# the_vert_annotated.net
KiCad netlist of a schematic drawn in EAGLE
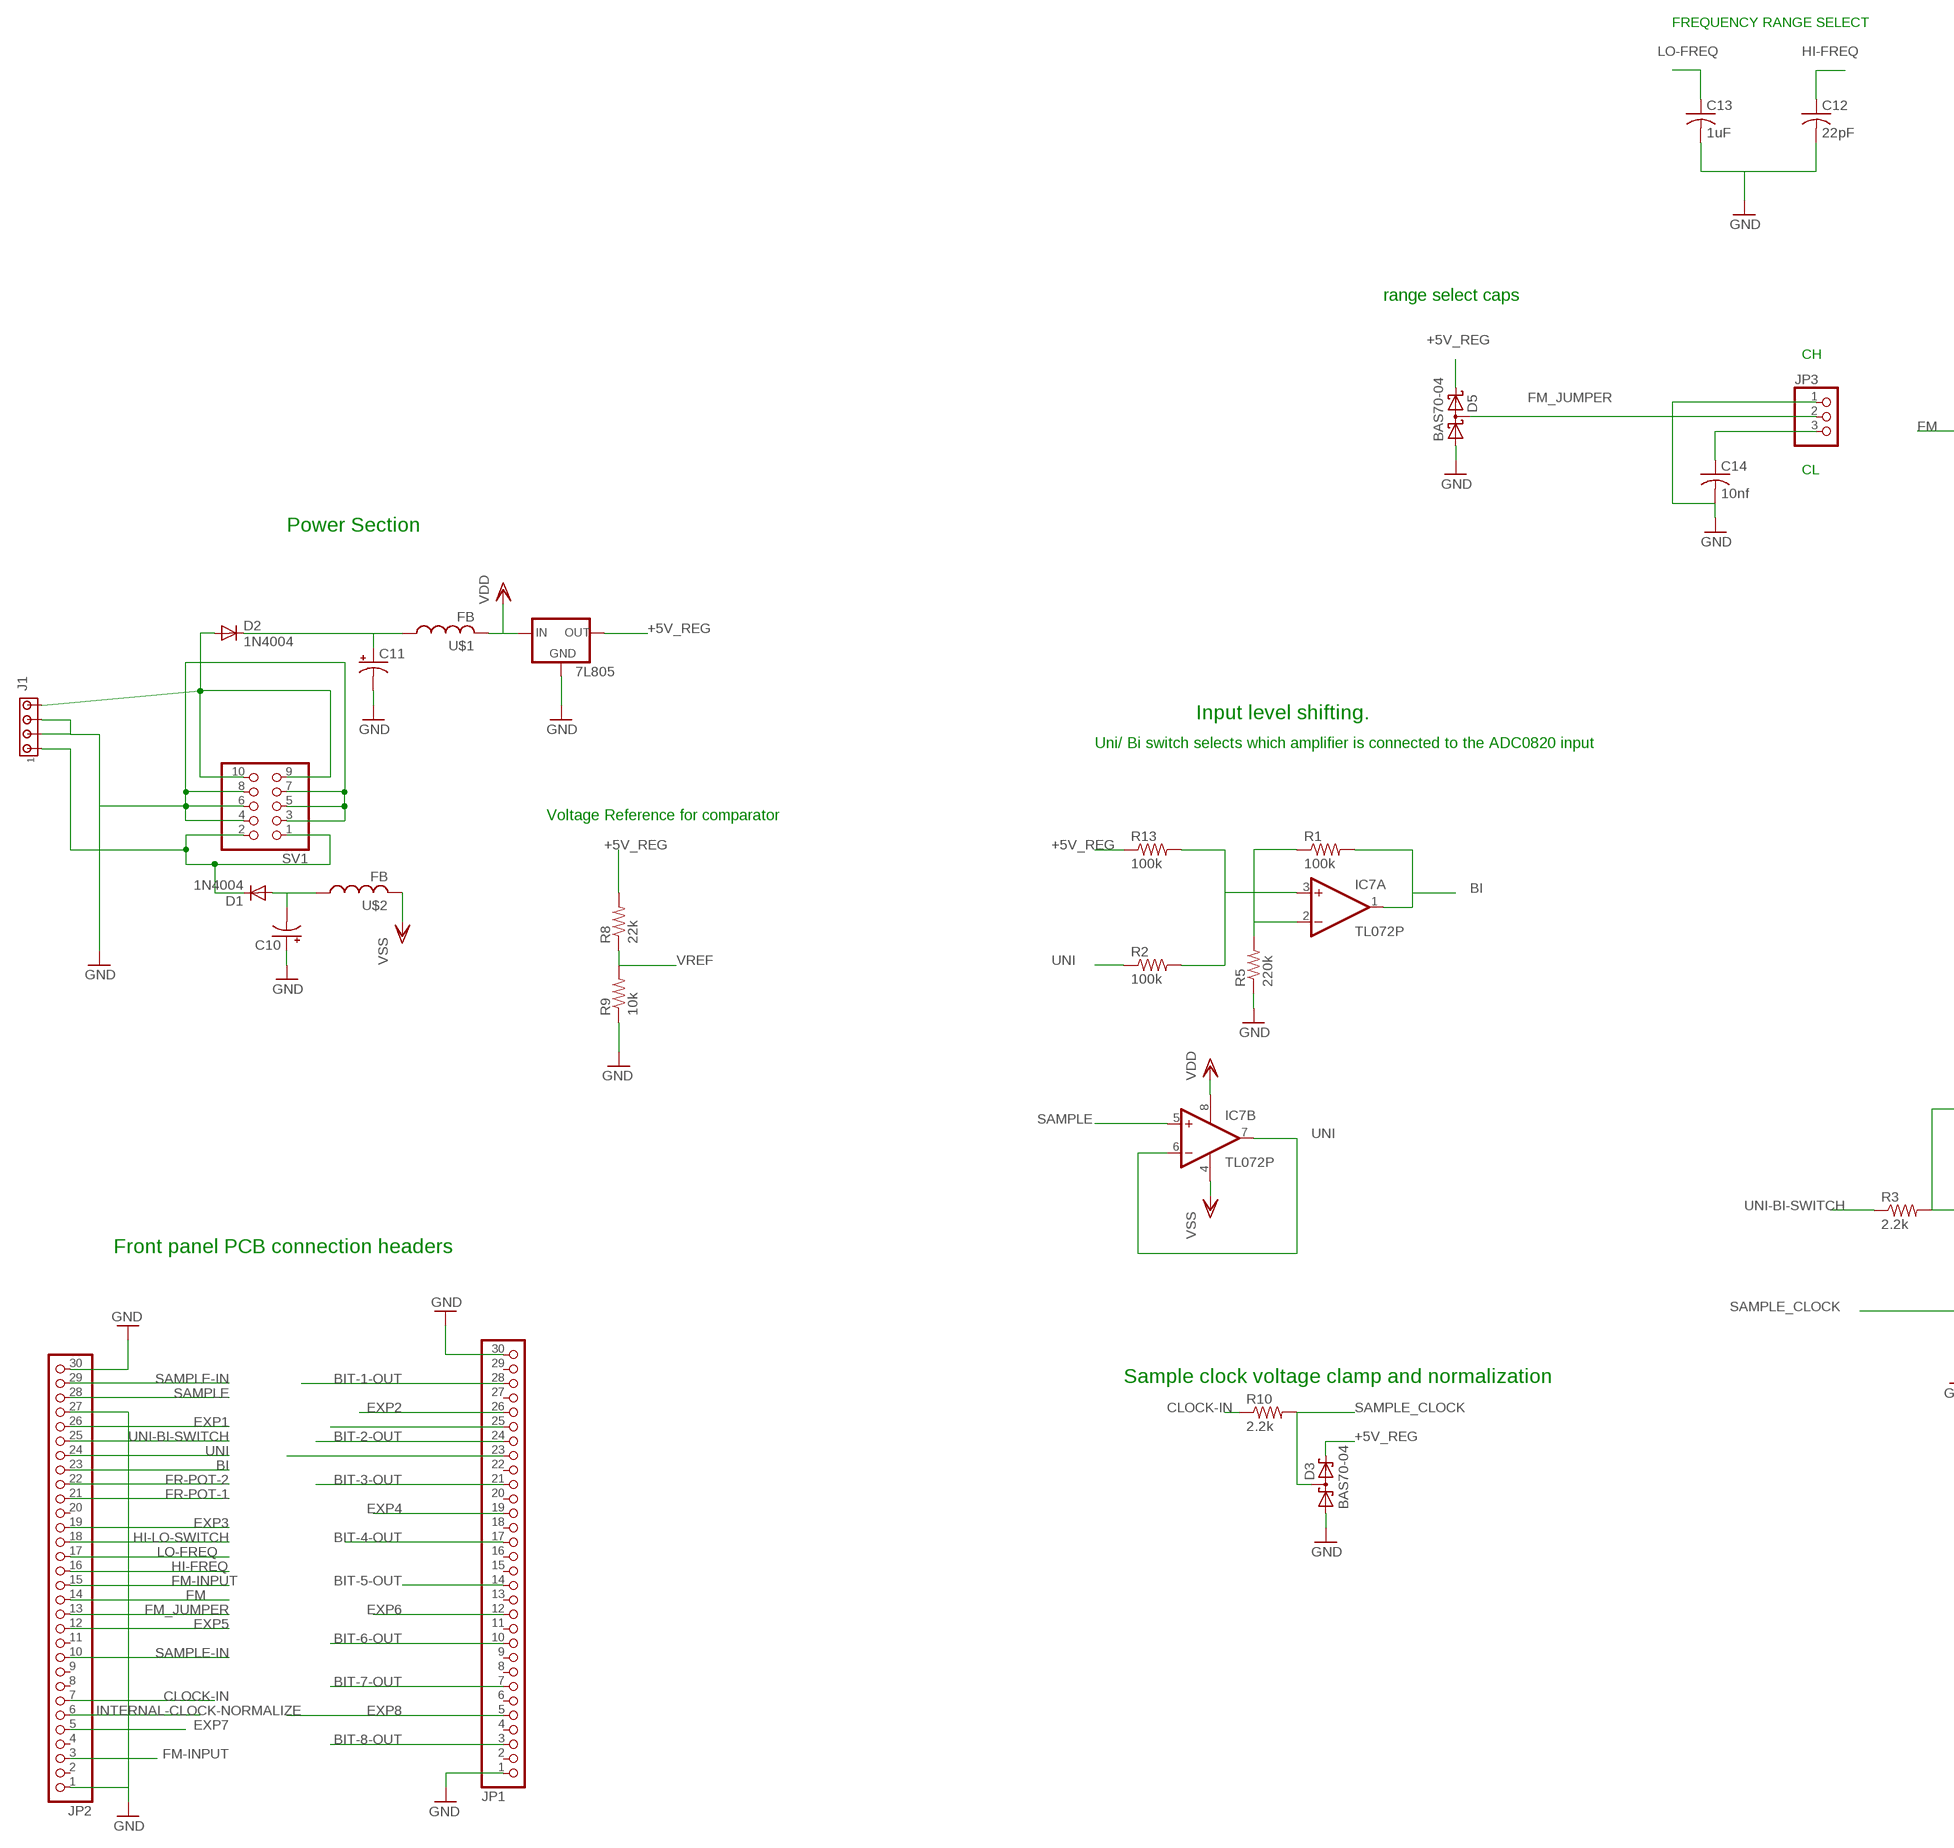
[diagram p0: schematic, sheet 1, part 1 of 2]
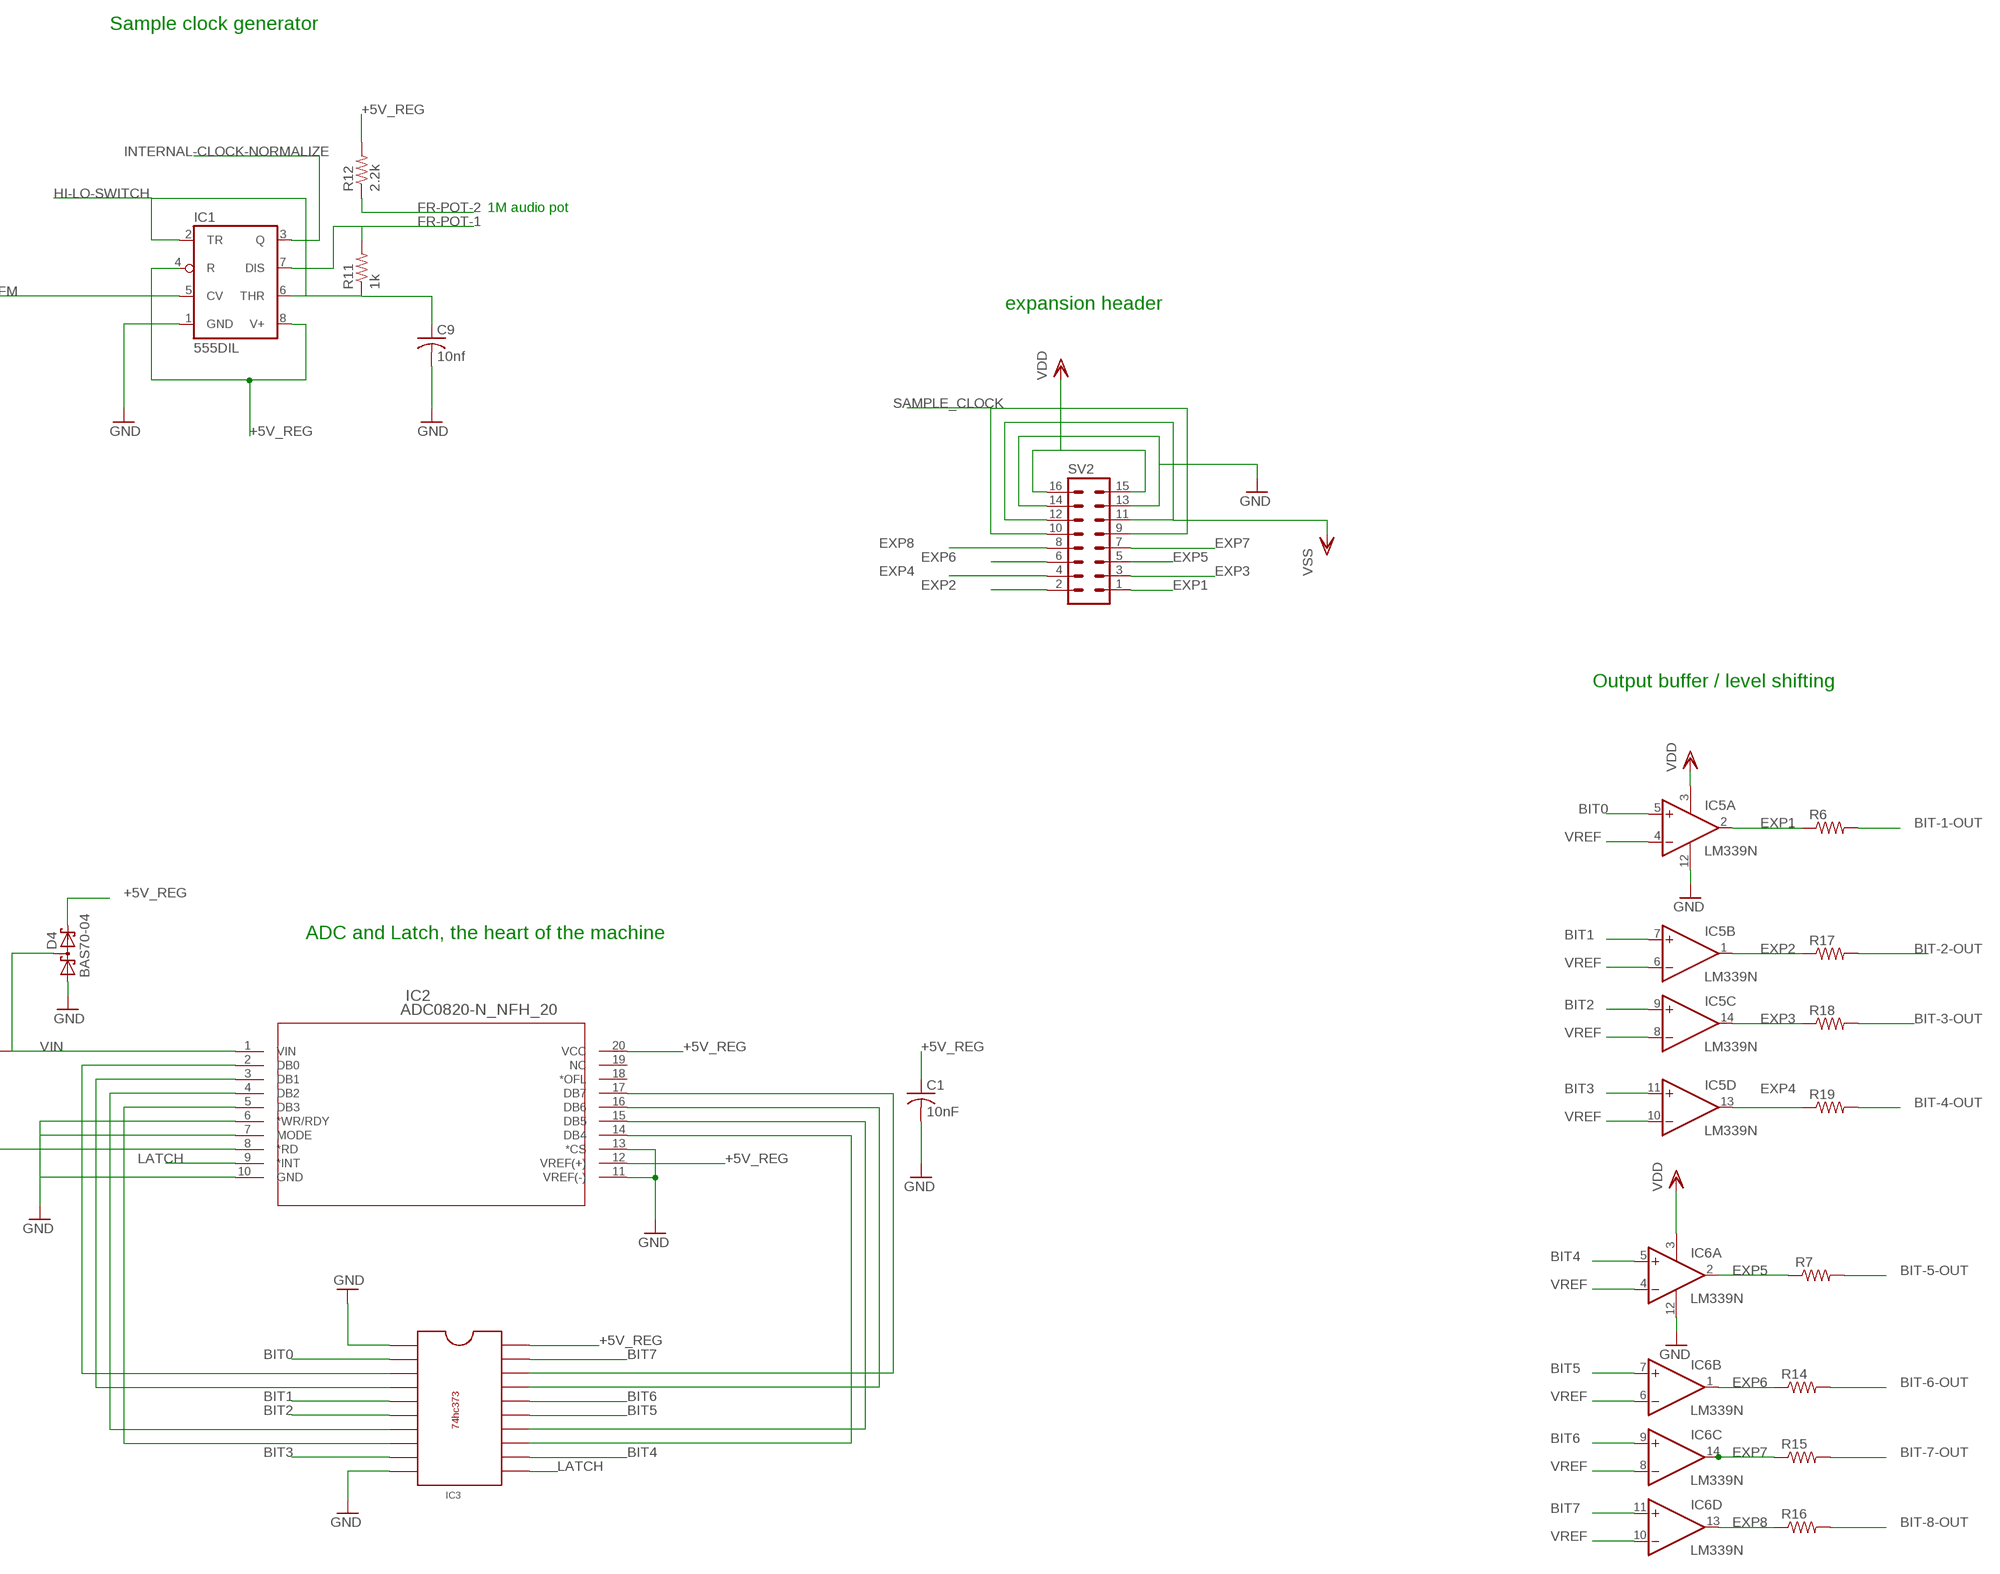
[diagram p1: schematic, sheet 1, part 2 of 2]

(export (version "E")
  (design (tool "Eeschema 10.0.6"))
  (components
    (comp (ref "7L805")
      (value "78LXX")
      (footprint "eagle-import:78LXX")
      (libsource (lib "eagle-import") (part "78LXX"))
    )
    (comp (ref "C1")
      (value "10nF")
      (footprint "eagle-import:C1206")
      (libsource (lib "eagle-import") (part "C-USC1206"))
    )
    (comp (ref "C9")
      (value "10nf")
      (footprint "eagle-import:C1206")
      (libsource (lib "eagle-import") (part "C-USC1206"))
    )
    (comp (ref "C10")
      (value "CPOL-USE5-5")
      (footprint "eagle-import:E5-5")
      (libsource (lib "eagle-import") (part "CPOL-USE5-5"))
    )
    (comp (ref "C11")
      (value "CPOL-USE5-5")
      (footprint "eagle-import:E5-5")
      (libsource (lib "eagle-import") (part "CPOL-USE5-5"))
    )
    (comp (ref "C12")
      (value "22pF")
      (footprint "eagle-import:C1206")
      (libsource (lib "eagle-import") (part "C-USC1206"))
    )
    (comp (ref "C13")
      (value "1uF")
      (footprint "eagle-import:C1206")
      (libsource (lib "eagle-import") (part "C-USC1206"))
    )
    (comp (ref "C14")
      (value "10nf")
      (footprint "eagle-import:C1206")
      (libsource (lib "eagle-import") (part "C-USC1206"))
    )
    (comp (ref "D1")
      (value "1N4004")
      (footprint "eagle-import:DO41-10")
      (libsource (lib "eagle-import") (part "1N4004"))
    )
    (comp (ref "D2")
      (value "1N4004")
      (footprint "eagle-import:DO41-10")
      (libsource (lib "eagle-import") (part "1N4004"))
    )
    (comp (ref "D3")
      (value "BAS70-04")
      (footprint "eagle-import:SOT23")
      (libsource (lib "eagle-import") (part "BAS70-04"))
    )
    (comp (ref "D4")
      (value "BAS70-04")
      (footprint "eagle-import:SOT23")
      (libsource (lib "eagle-import") (part "BAS70-04"))
    )
    (comp (ref "D5")
      (value "BAS70-04")
      (footprint "eagle-import:SOT23")
      (libsource (lib "eagle-import") (part "BAS70-04"))
    )
    (comp (ref "IC1")
      (value "555DIL")
      (footprint "eagle-import:DIL08")
      (libsource (lib "eagle-import") (part "555DIL"))
    )
    (comp (ref "IC2")
      (value "ADC0820-N_NFH_20")
      (footprint "eagle-import:NFH20")
      (fields (field (name "MANUFACTURER_PART_NUMBER") "adc0820_dw_20"))
      (libsource (lib "eagle-import") (part "ADC0820-N_NFH_20"))
    )
    (comp (ref "IC3")
      (value "74HC373")
      (footprint "eagle-import:DIL20")
      (libsource (lib "eagle-import") (part "74HC373"))
    )
    (comp (ref "IC5")
      (value "LM339N")
      (footprint "eagle-import:DIL14")
      (libsource (lib "eagle-import") (part "LM339N"))
    )
    (comp (ref "IC6")
      (value "LM339N")
      (footprint "eagle-import:DIL14")
      (libsource (lib "eagle-import") (part "LM339N"))
    )
    (comp (ref "IC7")
      (value "TL072P")
      (footprint "eagle-import:DIL08")
      (libsource (lib "eagle-import") (part "TL072P"))
    )
    (comp (ref "J1")
      (value "MTA04-156")
      (footprint "eagle-import:1X4MTA")
      (libsource (lib "eagle-import") (part "MTA04-156"))
    )
    (comp (ref "JP1")
      (value "PINHD-1X30")
      (footprint "eagle-import:1X30")
      (libsource (lib "eagle-import") (part "PINHD-1X30"))
    )
    (comp (ref "JP2")
      (value "PINHD-1X30")
      (footprint "eagle-import:1X30")
      (libsource (lib "eagle-import") (part "PINHD-1X30"))
    )
    (comp (ref "JP3")
      (value "PINHD-1X3")
      (footprint "eagle-import:1X03")
      (libsource (lib "eagle-import") (part "PINHD-1X3"))
    )
    (comp (ref "R1")
      (value "100k")
      (footprint "eagle-import:R1206")
      (libsource (lib "eagle-import") (part "R-US_R1206"))
    )
    (comp (ref "R2")
      (value "100k")
      (footprint "eagle-import:R1206")
      (libsource (lib "eagle-import") (part "R-US_R1206"))
    )
    (comp (ref "R3")
      (value "2.2k")
      (footprint "eagle-import:R1206")
      (libsource (lib "eagle-import") (part "R-US_R1206"))
    )
    (comp (ref "R5")
      (value "220k")
      (footprint "eagle-import:R1206")
      (libsource (lib "eagle-import") (part "R-US_R1206"))
    )
    (comp (ref "R6")
      (value "R-US_R1206")
      (footprint "eagle-import:R1206")
      (libsource (lib "eagle-import") (part "R-US_R1206"))
    )
    (comp (ref "R7")
      (value "R-US_R1206")
      (footprint "eagle-import:R1206")
      (libsource (lib "eagle-import") (part "R-US_R1206"))
    )
    (comp (ref "R8")
      (value "22k")
      (footprint "eagle-import:R1206")
      (libsource (lib "eagle-import") (part "R-US_R1206"))
    )
    (comp (ref "R9")
      (value "10k")
      (footprint "eagle-import:R1206")
      (libsource (lib "eagle-import") (part "R-US_R1206"))
    )
    (comp (ref "R10")
      (value "2.2k")
      (footprint "eagle-import:R1206")
      (libsource (lib "eagle-import") (part "R-US_R1206"))
    )
    (comp (ref "R11")
      (value "1k")
      (footprint "eagle-import:R1206")
      (libsource (lib "eagle-import") (part "R-US_R1206"))
    )
    (comp (ref "R12")
      (value "2.2k")
      (footprint "eagle-import:R1206")
      (libsource (lib "eagle-import") (part "R-US_R1206"))
    )
    (comp (ref "R13")
      (value "100k")
      (footprint "eagle-import:R1206")
      (libsource (lib "eagle-import") (part "R-US_R1206"))
    )
    (comp (ref "R14")
      (value "R-US_R1206")
      (footprint "eagle-import:R1206")
      (libsource (lib "eagle-import") (part "R-US_R1206"))
    )
    (comp (ref "R15")
      (value "R-US_R1206")
      (footprint "eagle-import:R1206")
      (libsource (lib "eagle-import") (part "R-US_R1206"))
    )
    (comp (ref "R16")
      (value "R-US_R1206")
      (footprint "eagle-import:R1206")
      (libsource (lib "eagle-import") (part "R-US_R1206"))
    )
    (comp (ref "R17")
      (value "R-US_R1206")
      (footprint "eagle-import:R1206")
      (libsource (lib "eagle-import") (part "R-US_R1206"))
    )
    (comp (ref "R18")
      (value "R-US_R1206")
      (footprint "eagle-import:R1206")
      (libsource (lib "eagle-import") (part "R-US_R1206"))
    )
    (comp (ref "R19")
      (value "R-US_R1206")
      (footprint "eagle-import:R1206")
      (libsource (lib "eagle-import") (part "R-US_R1206"))
    )
    (comp (ref "SV1")
      (value "PINHD-2X5")
      (footprint "eagle-import:2X05")
      (libsource (lib "eagle-import") (part "PINHD-2X5"))
    )
    (comp (ref "SV2")
      (value "MA08-2")
      (footprint "eagle-import:MA08-2")
      (libsource (lib "eagle-import") (part "MA08-2"))
    )
    (comp (ref "U$1") (value "FB") (footprint "eagle-import:FB") (libsource (lib "eagle-import") (part "FB")))
    (comp (ref "U$2") (value "FB") (footprint "eagle-import:FB") (libsource (lib "eagle-import") (part "FB")))
  )
  (nets
    (net (code "1") (name "/+5V_REG") (class "Default")
      (node (ref "7L805") (pin "OUT") (pinfunction "OUT_OUT") (pintype "passive"))
      (node (ref "C1") (pin "1") (pinfunction "1_1") (pintype "passive"))
      (node (ref "D3") (pin "2") (pinfunction "C2_2") (pintype "passive"))
      (node (ref "D4") (pin "2") (pinfunction "C2_2") (pintype "passive"))
      (node (ref "D5") (pin "2") (pinfunction "C2_2") (pintype "passive"))
      (node (ref "IC1") (pin "4") (pinfunction "R_4") (pintype "input"))
      (node (ref "IC1") (pin "8") (pinfunction "V+_8") (pintype "power_in"))
      (node (ref "IC2") (pin "12") (pinfunction "VREF(+)_12") (pintype "power_in"))
      (node (ref "IC2") (pin "20") (pinfunction "VCC_20") (pintype "power_in"))
      (node (ref "IC3") (pin "20") (pinfunction "20_20") (pintype "bidirectional"))
      (node (ref "R12") (pin "2") (pinfunction "2_2") (pintype "passive"))
      (node (ref "R13") (pin "1") (pinfunction "1_1") (pintype "passive"))
      (node (ref "R8") (pin "2") (pinfunction "2_2") (pintype "passive"))
    )
    (net (code "2") (name "/BI") (class "Default")
      (node (ref "IC7") (pin "1") (pinfunction "OUT_1") (pintype "output"))
      (node (ref "JP2") (pin "23") (pinfunction "23_23") (pintype "passive"))
      (node (ref "R1") (pin "2") (pinfunction "2_2") (pintype "passive"))
    )
    (net (code "3") (name "/BIT-1-OUT") (class "Default")
      (node (ref "JP1") (pin "28") (pinfunction "28_28") (pintype "passive"))
      (node (ref "R6") (pin "2") (pinfunction "2_2") (pintype "passive"))
    )
    (net (code "4") (name "/BIT-2-OUT") (class "Default")
      (node (ref "JP1") (pin "24") (pinfunction "24_24") (pintype "passive"))
      (node (ref "R17") (pin "2") (pinfunction "2_2") (pintype "passive"))
    )
    (net (code "5") (name "/BIT-3-OUT") (class "Default")
      (node (ref "JP1") (pin "21") (pinfunction "21_21") (pintype "passive"))
      (node (ref "R18") (pin "2") (pinfunction "2_2") (pintype "passive"))
    )
    (net (code "6") (name "/BIT-4-OUT") (class "Default")
      (node (ref "JP1") (pin "17") (pinfunction "17_17") (pintype "passive"))
      (node (ref "R19") (pin "2") (pinfunction "2_2") (pintype "passive"))
    )
    (net (code "7") (name "/BIT-5-OUT") (class "Default")
      (node (ref "JP1") (pin "14") (pinfunction "14_14") (pintype "passive"))
      (node (ref "R7") (pin "2") (pinfunction "2_2") (pintype "passive"))
    )
    (net (code "8") (name "/BIT-6-OUT") (class "Default")
      (node (ref "JP1") (pin "10") (pinfunction "10_10") (pintype "passive"))
      (node (ref "R14") (pin "2") (pinfunction "2_2") (pintype "passive"))
    )
    (net (code "9") (name "/BIT-7-OUT") (class "Default")
      (node (ref "JP1") (pin "7") (pinfunction "7_7") (pintype "passive"))
      (node (ref "R15") (pin "2") (pinfunction "2_2") (pintype "passive"))
    )
    (net (code "10") (name "/BIT-8-OUT") (class "Default")
      (node (ref "JP1") (pin "3") (pinfunction "3_3") (pintype "passive"))
      (node (ref "R16") (pin "2") (pinfunction "2_2") (pintype "passive"))
    )
    (net (code "11") (name "/BIT0") (class "Default")
      (node (ref "IC3") (pin "2") (pinfunction "2_2") (pintype "bidirectional"))
      (node (ref "IC5") (pin "5") (pinfunction "+IN_5") (pintype "input"))
    )
    (net (code "12") (name "/BIT1") (class "Default")
      (node (ref "IC3") (pin "5") (pinfunction "5_5") (pintype "bidirectional"))
      (node (ref "IC5") (pin "7") (pinfunction "+IN_7") (pintype "input"))
    )
    (net (code "13") (name "/BIT2") (class "Default")
      (node (ref "IC3") (pin "6") (pinfunction "6_6") (pintype "bidirectional"))
      (node (ref "IC5") (pin "9") (pinfunction "+IN_9") (pintype "input"))
    )
    (net (code "14") (name "/BIT3") (class "Default")
      (node (ref "IC3") (pin "9") (pinfunction "9_9") (pintype "bidirectional"))
      (node (ref "IC5") (pin "11") (pinfunction "+IN_11") (pintype "input"))
    )
    (net (code "15") (name "/BIT4") (class "Default")
      (node (ref "IC3") (pin "12") (pinfunction "12_12") (pintype "bidirectional"))
      (node (ref "IC6") (pin "5") (pinfunction "+IN_5") (pintype "input"))
    )
    (net (code "16") (name "/BIT5") (class "Default")
      (node (ref "IC3") (pin "15") (pinfunction "15_15") (pintype "bidirectional"))
      (node (ref "IC6") (pin "7") (pinfunction "+IN_7") (pintype "input"))
    )
    (net (code "17") (name "/BIT6") (class "Default")
      (node (ref "IC3") (pin "16") (pinfunction "16_16") (pintype "bidirectional"))
      (node (ref "IC6") (pin "9") (pinfunction "+IN_9") (pintype "input"))
    )
    (net (code "18") (name "/BIT7") (class "Default")
      (node (ref "IC3") (pin "19") (pinfunction "19_19") (pintype "bidirectional"))
      (node (ref "IC6") (pin "11") (pinfunction "+IN_11") (pintype "input"))
    )
    (net (code "19") (name "/CLOCK-IN") (class "Default")
      (node (ref "JP2") (pin "7") (pinfunction "7_7") (pintype "passive"))
      (node (ref "R10") (pin "1") (pinfunction "1_1") (pintype "passive"))
    )
    (net (code "20") (name "/EXP1") (class "Default")
      (node (ref "IC5") (pin "2") (pinfunction "OUT_2") (pintype "open_collector"))
      (node (ref "JP2") (pin "26") (pinfunction "26_26") (pintype "passive"))
      (node (ref "R6") (pin "1") (pinfunction "1_1") (pintype "passive"))
      (node (ref "SV2") (pin "1") (pinfunction "1_1") (pintype "passive"))
    )
    (net (code "21") (name "/EXP2") (class "Default")
      (node (ref "IC5") (pin "1") (pinfunction "OUT_1") (pintype "open_collector"))
      (node (ref "JP1") (pin "26") (pinfunction "26_26") (pintype "passive"))
      (node (ref "R17") (pin "1") (pinfunction "1_1") (pintype "passive"))
      (node (ref "SV2") (pin "2") (pinfunction "2_2") (pintype "passive"))
    )
    (net (code "22") (name "/EXP3") (class "Default")
      (node (ref "IC5") (pin "14") (pinfunction "OUT_14") (pintype "open_collector"))
      (node (ref "JP2") (pin "19") (pinfunction "19_19") (pintype "passive"))
      (node (ref "R18") (pin "1") (pinfunction "1_1") (pintype "passive"))
      (node (ref "SV2") (pin "3") (pinfunction "3_3") (pintype "passive"))
    )
    (net (code "23") (name "/EXP4") (class "Default")
      (node (ref "IC5") (pin "13") (pinfunction "OUT_13") (pintype "open_collector"))
      (node (ref "JP1") (pin "19") (pinfunction "19_19") (pintype "passive"))
      (node (ref "R19") (pin "1") (pinfunction "1_1") (pintype "passive"))
      (node (ref "SV2") (pin "4") (pinfunction "4_4") (pintype "passive"))
    )
    (net (code "24") (name "/EXP5") (class "Default")
      (node (ref "IC6") (pin "2") (pinfunction "OUT_2") (pintype "open_collector"))
      (node (ref "JP2") (pin "12") (pinfunction "12_12") (pintype "passive"))
      (node (ref "R7") (pin "1") (pinfunction "1_1") (pintype "passive"))
      (node (ref "SV2") (pin "5") (pinfunction "5_5") (pintype "passive"))
    )
    (net (code "25") (name "/EXP6") (class "Default")
      (node (ref "IC6") (pin "1") (pinfunction "OUT_1") (pintype "open_collector"))
      (node (ref "JP1") (pin "12") (pinfunction "12_12") (pintype "passive"))
      (node (ref "R14") (pin "1") (pinfunction "1_1") (pintype "passive"))
      (node (ref "SV2") (pin "6") (pinfunction "6_6") (pintype "passive"))
    )
    (net (code "26") (name "/EXP7") (class "Default")
      (node (ref "IC6") (pin "14") (pinfunction "OUT_14") (pintype "open_collector"))
      (node (ref "JP2") (pin "5") (pinfunction "5_5") (pintype "passive"))
      (node (ref "R15") (pin "1") (pinfunction "1_1") (pintype "passive"))
      (node (ref "SV2") (pin "7") (pinfunction "7_7") (pintype "passive"))
    )
    (net (code "27") (name "/EXP8") (class "Default")
      (node (ref "IC6") (pin "13") (pinfunction "OUT_13") (pintype "open_collector"))
      (node (ref "JP1") (pin "5") (pinfunction "5_5") (pintype "passive"))
      (node (ref "R16") (pin "1") (pinfunction "1_1") (pintype "passive"))
      (node (ref "SV2") (pin "8") (pinfunction "8_8") (pintype "passive"))
    )
    (net (code "28") (name "/FM") (class "Default")
      (node (ref "IC1") (pin "5") (pinfunction "CV_5") (pintype "input"))
      (node (ref "JP2") (pin "14") (pinfunction "14_14") (pintype "passive"))
    )
    (net (code "29") (name "/FM-INPUT") (class "Default")
      (node (ref "JP2") (pin "15") (pinfunction "15_15") (pintype "passive"))
      (node (ref "JP2") (pin "3") (pinfunction "3_3") (pintype "passive"))
    )
    (net (code "30") (name "/FM_JUMPER") (class "Default")
      (node (ref "D5") (pin "3") (pinfunction "C1A2_3") (pintype "passive"))
      (node (ref "JP2") (pin "13") (pinfunction "13_13") (pintype "passive"))
      (node (ref "JP3") (pin "2") (pinfunction "2_2") (pintype "passive"))
    )
    (net (code "31") (name "/FR-POT-1") (class "Default")
      (node (ref "IC1") (pin "7") (pinfunction "DIS_7") (pintype "input"))
      (node (ref "JP2") (pin "21") (pinfunction "21_21") (pintype "passive"))
      (node (ref "R11") (pin "2") (pinfunction "2_2") (pintype "passive"))
    )
    (net (code "32") (name "/FR-POT-2") (class "Default")
      (node (ref "JP2") (pin "22") (pinfunction "22_22") (pintype "passive"))
      (node (ref "R12") (pin "1") (pinfunction "1_1") (pintype "passive"))
    )
    (net (code "33") (name "/HI-FREQ") (class "Default")
      (node (ref "C12") (pin "1") (pinfunction "1_1") (pintype "passive"))
      (node (ref "JP2") (pin "16") (pinfunction "16_16") (pintype "passive"))
    )
    (net (code "34") (name "/HI-LO-SWITCH") (class "Default")
      (node (ref "C9") (pin "1") (pinfunction "1_1") (pintype "passive"))
      (node (ref "IC1") (pin "2") (pinfunction "TR_2") (pintype "input"))
      (node (ref "IC1") (pin "6") (pinfunction "THR_6") (pintype "input"))
      (node (ref "JP2") (pin "18") (pinfunction "18_18") (pintype "passive"))
      (node (ref "R11") (pin "1") (pinfunction "1_1") (pintype "passive"))
    )
    (net (code "35") (name "/INTERNAL-CLOCK-NORMALIZE") (class "Default")
      (node (ref "IC1") (pin "3") (pinfunction "Q_3") (pintype "output"))
      (node (ref "JP2") (pin "6") (pinfunction "6_6") (pintype "passive"))
    )
    (net (code "36") (name "/LATCH") (class "Default")
      (node (ref "IC2") (pin "9") (pinfunction "*INT_9") (pintype "passive"))
      (node (ref "IC3") (pin "11") (pinfunction "11_11") (pintype "bidirectional"))
    )
    (net (code "37") (name "/LO-FREQ") (class "Default")
      (node (ref "C13") (pin "1") (pinfunction "1_1") (pintype "passive"))
      (node (ref "JP2") (pin "17") (pinfunction "17_17") (pintype "passive"))
    )
    (net (code "38") (name "/SAMPLE") (class "Default")
      (node (ref "IC7") (pin "5") (pinfunction "+IN_5") (pintype "input"))
      (node (ref "JP2") (pin "28") (pinfunction "28_28") (pintype "passive"))
    )
    (net (code "39") (name "/SAMPLE-IN") (class "Default")
      (node (ref "JP2") (pin "10") (pinfunction "10_10") (pintype "passive"))
      (node (ref "JP2") (pin "29") (pinfunction "29_29") (pintype "passive"))
    )
    (net (code "40") (name "/SAMPLE_CLOCK") (class "Default")
      (node (ref "D3") (pin "3") (pinfunction "C1A2_3") (pintype "passive"))
      (node (ref "IC2") (pin "8") (pinfunction "*RD_8") (pintype "output"))
      (node (ref "R10") (pin "2") (pinfunction "2_2") (pintype "passive"))
      (node (ref "SV2") (pin "10") (pinfunction "10_10") (pintype "passive"))
      (node (ref "SV2") (pin "9") (pinfunction "9_9") (pintype "passive"))
    )
    (net (code "41") (name "/UNI") (class "Default")
      (node (ref "IC7") (pin "6") (pinfunction "-IN_6") (pintype "input"))
      (node (ref "IC7") (pin "7") (pinfunction "OUT_7") (pintype "output"))
      (node (ref "JP2") (pin "24") (pinfunction "24_24") (pintype "passive"))
      (node (ref "R2") (pin "1") (pinfunction "1_1") (pintype "passive"))
    )
    (net (code "42") (name "/UNI-BI-SWITCH") (class "Default")
      (node (ref "JP2") (pin "25") (pinfunction "25_25") (pintype "passive"))
      (node (ref "R3") (pin "1") (pinfunction "1_1") (pintype "passive"))
    )
    (net (code "43") (name "/VIN") (class "Default")
      (node (ref "D4") (pin "3") (pinfunction "C1A2_3") (pintype "passive"))
      (node (ref "IC2") (pin "1") (pinfunction "VIN_1") (pintype "input"))
      (node (ref "R3") (pin "2") (pinfunction "2_2") (pintype "passive"))
    )
    (net (code "44") (name "/VREF") (class "Default")
      (node (ref "IC5") (pin "10") (pinfunction "-IN_10") (pintype "input"))
      (node (ref "IC5") (pin "4") (pinfunction "-IN_4") (pintype "input"))
      (node (ref "IC5") (pin "6") (pinfunction "-IN_6") (pintype "input"))
      (node (ref "IC5") (pin "8") (pinfunction "-IN_8") (pintype "input"))
      (node (ref "IC6") (pin "10") (pinfunction "-IN_10") (pintype "input"))
      (node (ref "IC6") (pin "4") (pinfunction "-IN_4") (pintype "input"))
      (node (ref "IC6") (pin "6") (pinfunction "-IN_6") (pintype "input"))
      (node (ref "IC6") (pin "8") (pinfunction "-IN_8") (pintype "input"))
      (node (ref "R8") (pin "1") (pinfunction "1_1") (pintype "passive"))
      (node (ref "R9") (pin "2") (pinfunction "2_2") (pintype "passive"))
    )
    (net (code "45") (name "GND") (class "Default")
      (node (ref "7L805") (pin "GND") (pinfunction "GND_GND") (pintype "input"))
      (node (ref "C1") (pin "2") (pinfunction "2_2") (pintype "passive"))
      (node (ref "C10") (pin "+") (pinfunction "+_+") (pintype "passive"))
      (node (ref "C11") (pin "-") (pinfunction "-_-") (pintype "passive"))
      (node (ref "C12") (pin "2") (pinfunction "2_2") (pintype "passive"))
      (node (ref "C13") (pin "2") (pinfunction "2_2") (pintype "passive"))
      (node (ref "C14") (pin "2") (pinfunction "2_2") (pintype "passive"))
      (node (ref "C9") (pin "2") (pinfunction "2_2") (pintype "passive"))
      (node (ref "D3") (pin "1") (pinfunction "A1_1") (pintype "passive"))
      (node (ref "D4") (pin "1") (pinfunction "A1_1") (pintype "passive"))
      (node (ref "D5") (pin "1") (pinfunction "A1_1") (pintype "passive"))
      (node (ref "IC1") (pin "1") (pinfunction "GND_1") (pintype "power_in"))
      (node (ref "IC2") (pin "10") (pinfunction "GND_10") (pintype "power_in"))
      (node (ref "IC2") (pin "11") (pinfunction "VREF(-)_11") (pintype "power_in"))
      (node (ref "IC2") (pin "13") (pinfunction "*CS_13") (pintype "passive"))
      (node (ref "IC2") (pin "6") (pinfunction "*WR/RDY_6") (pintype "bidirectional"))
      (node (ref "IC2") (pin "7") (pinfunction "MODE_7") (pintype "input"))
      (node (ref "IC3") (pin "1") (pinfunction "1_1") (pintype "bidirectional"))
      (node (ref "IC3") (pin "10") (pinfunction "10_10") (pintype "bidirectional"))
      (node (ref "IC5") (pin "12") (pinfunction "GND_12") (pintype "power_in"))
      (node (ref "IC6") (pin "12") (pinfunction "GND_12") (pintype "power_in"))
      (node (ref "J1") (pin "2") (pinfunction "2_2") (pintype "passive"))
      (node (ref "J1") (pin "3") (pinfunction "3_3") (pintype "passive"))
      (node (ref "JP1") (pin "1") (pinfunction "1_1") (pintype "passive"))
      (node (ref "JP1") (pin "30") (pinfunction "30_30") (pintype "passive"))
      (node (ref "JP2") (pin "1") (pinfunction "1_1") (pintype "passive"))
      (node (ref "JP2") (pin "27") (pinfunction "27_27") (pintype "passive"))
      (node (ref "JP2") (pin "30") (pinfunction "30_30") (pintype "passive"))
      (node (ref "JP3") (pin "1") (pinfunction "1_1") (pintype "passive"))
      (node (ref "R5") (pin "1") (pinfunction "1_1") (pintype "passive"))
      (node (ref "R9") (pin "1") (pinfunction "1_1") (pintype "passive"))
      (node (ref "SV1") (pin "3") (pinfunction "3_3") (pintype "passive"))
      (node (ref "SV1") (pin "4") (pinfunction "4_4") (pintype "passive"))
      (node (ref "SV1") (pin "5") (pinfunction "5_5") (pintype "passive"))
      (node (ref "SV1") (pin "6") (pinfunction "6_6") (pintype "passive"))
      (node (ref "SV1") (pin "7") (pinfunction "7_7") (pintype "passive"))
      (node (ref "SV1") (pin "8") (pinfunction "8_8") (pintype "passive"))
      (node (ref "SV2") (pin "13") (pinfunction "13_13") (pintype "passive"))
      (node (ref "SV2") (pin "14") (pinfunction "14_14") (pintype "passive"))
    )
    (net (code "46") (name "Net-(C14-Pad1)") (class "Default")
      (node (ref "C14") (pin "1") (pinfunction "1_1") (pintype "passive"))
      (node (ref "JP3") (pin "3") (pinfunction "3_3") (pintype "passive"))
    )
    (net (code "47") (name "Net-(D1-PadC)") (class "Default")
      (node (ref "D1") (pin "C") (pinfunction "C_C") (pintype "passive"))
      (node (ref "J1") (pin "1") (pinfunction "1_1") (pintype "passive"))
      (node (ref "SV1") (pin "1") (pinfunction "1_1") (pintype "passive"))
      (node (ref "SV1") (pin "2") (pinfunction "2_2") (pintype "passive"))
    )
    (net (code "48") (name "Net-(D2-PadA)") (class "Default")
      (node (ref "D2") (pin "A") (pinfunction "A_A") (pintype "passive"))
      (node (ref "J1") (pin "4") (pinfunction "4_4") (pintype "passive"))
      (node (ref "SV1") (pin "10") (pinfunction "10_10") (pintype "passive"))
      (node (ref "SV1") (pin "9") (pinfunction "9_9") (pintype "passive"))
    )
    (net (code "49") (name "Net-(IC2-DB0)") (class "Default")
      (node (ref "IC2") (pin "2") (pinfunction "DB0_2") (pintype "bidirectional"))
      (node (ref "IC3") (pin "3") (pinfunction "3_3") (pintype "bidirectional"))
    )
    (net (code "50") (name "Net-(IC2-DB1)") (class "Default")
      (node (ref "IC2") (pin "3") (pinfunction "DB1_3") (pintype "bidirectional"))
      (node (ref "IC3") (pin "4") (pinfunction "4_4") (pintype "bidirectional"))
    )
    (net (code "51") (name "Net-(IC2-DB2)") (class "Default")
      (node (ref "IC2") (pin "4") (pinfunction "DB2_4") (pintype "bidirectional"))
      (node (ref "IC3") (pin "7") (pinfunction "7_7") (pintype "bidirectional"))
    )
    (net (code "52") (name "Net-(IC2-DB3)") (class "Default")
      (node (ref "IC2") (pin "5") (pinfunction "DB3_5") (pintype "bidirectional"))
      (node (ref "IC3") (pin "8") (pinfunction "8_8") (pintype "bidirectional"))
    )
    (net (code "53") (name "Net-(IC2-DB4)") (class "Default")
      (node (ref "IC2") (pin "14") (pinfunction "DB4_14") (pintype "bidirectional"))
      (node (ref "IC3") (pin "13") (pinfunction "13_13") (pintype "bidirectional"))
    )
    (net (code "54") (name "Net-(IC2-DB5)") (class "Default")
      (node (ref "IC2") (pin "15") (pinfunction "DB5_15") (pintype "bidirectional"))
      (node (ref "IC3") (pin "14") (pinfunction "14_14") (pintype "bidirectional"))
    )
    (net (code "55") (name "Net-(IC2-DB6)") (class "Default")
      (node (ref "IC2") (pin "16") (pinfunction "DB6_16") (pintype "bidirectional"))
      (node (ref "IC3") (pin "17") (pinfunction "17_17") (pintype "bidirectional"))
    )
    (net (code "56") (name "Net-(IC2-DB7)") (class "Default")
      (node (ref "IC2") (pin "17") (pinfunction "DB7_17") (pintype "bidirectional"))
      (node (ref "IC3") (pin "18") (pinfunction "18_18") (pintype "bidirectional"))
    )
    (net (code "57") (name "Net-(IC7A-+IN)") (class "Default")
      (node (ref "IC7") (pin "3") (pinfunction "+IN_3") (pintype "input"))
      (node (ref "R13") (pin "2") (pinfunction "2_2") (pintype "passive"))
      (node (ref "R2") (pin "2") (pinfunction "2_2") (pintype "passive"))
    )
    (net (code "58") (name "Net-(IC7A--IN)") (class "Default")
      (node (ref "IC7") (pin "2") (pinfunction "-IN_2") (pintype "input"))
      (node (ref "R1") (pin "1") (pinfunction "1_1") (pintype "passive"))
      (node (ref "R5") (pin "2") (pinfunction "2_2") (pintype "passive"))
    )
    (net (code "59") (name "Net-(U$1-1)") (class "Default")
      (node (ref "C11") (pin "+") (pinfunction "+_+") (pintype "passive"))
      (node (ref "D2") (pin "C") (pinfunction "C_C") (pintype "passive"))
      (node (ref "U$1") (pin "P$1") (pinfunction "1_P$1") (pintype "passive"))
    )
    (net (code "60") (name "Net-(U$2-1)") (class "Default")
      (node (ref "C10") (pin "-") (pinfunction "-_-") (pintype "passive"))
      (node (ref "D1") (pin "A") (pinfunction "A_A") (pintype "passive"))
      (node (ref "U$2") (pin "P$1") (pinfunction "1_P$1") (pintype "passive"))
    )
    (net (code "61") (name "VDD") (class "Default")
      (node (ref "7L805") (pin "IN") (pinfunction "IN_IN") (pintype "input"))
      (node (ref "IC5") (pin "3") (pinfunction "V+_3") (pintype "power_in"))
      (node (ref "IC6") (pin "3") (pinfunction "V+_3") (pintype "power_in"))
      (node (ref "IC7") (pin "8") (pinfunction "V+_8") (pintype "power_in"))
      (node (ref "SV2") (pin "15") (pinfunction "15_15") (pintype "passive"))
      (node (ref "SV2") (pin "16") (pinfunction "16_16") (pintype "passive"))
      (node (ref "U$1") (pin "P$2") (pinfunction "2_P$2") (pintype "passive"))
    )
    (net (code "62") (name "VSS") (class "Default")
      (node (ref "IC7") (pin "4") (pinfunction "V-_4") (pintype "power_in"))
      (node (ref "SV2") (pin "11") (pinfunction "11_11") (pintype "passive"))
      (node (ref "SV2") (pin "12") (pinfunction "12_12") (pintype "passive"))
      (node (ref "U$2") (pin "P$2") (pinfunction "2_P$2") (pintype "passive"))
    )
    (net (code "63") (name "unconnected-(IC2-*OFL-Pad18)") (class "Default")
      (node (ref "IC2") (pin "18") (pinfunction "*OFL_18") (pintype "output"))
    )
    (net (code "64") (name "unconnected-(IC2-NC-Pad19)") (class "Default")
      (node (ref "IC2") (pin "19") (pinfunction "NC_19") (pintype "no_connect"))
    )
    (net (code "65") (name "unconnected-(JP1-Pad2)") (class "Default")
      (node (ref "JP1") (pin "2") (pinfunction "2_2") (pintype "passive"))
    )
    (net (code "66") (name "unconnected-(JP1-Pad4)") (class "Default")
      (node (ref "JP1") (pin "4") (pinfunction "4_4") (pintype "passive"))
    )
    (net (code "67") (name "unconnected-(JP1-Pad6)") (class "Default")
      (node (ref "JP1") (pin "6") (pinfunction "6_6") (pintype "passive"))
    )
    (net (code "68") (name "unconnected-(JP1-Pad8)") (class "Default")
      (node (ref "JP1") (pin "8") (pinfunction "8_8") (pintype "passive"))
    )
    (net (code "69") (name "unconnected-(JP1-Pad9)") (class "Default")
      (node (ref "JP1") (pin "9") (pinfunction "9_9") (pintype "passive"))
    )
    (net (code "70") (name "unconnected-(JP1-Pad11)") (class "Default")
      (node (ref "JP1") (pin "11") (pinfunction "11_11") (pintype "passive"))
    )
    (net (code "71") (name "unconnected-(JP1-Pad13)") (class "Default")
      (node (ref "JP1") (pin "13") (pinfunction "13_13") (pintype "passive"))
    )
    (net (code "72") (name "unconnected-(JP1-Pad15)") (class "Default")
      (node (ref "JP1") (pin "15") (pinfunction "15_15") (pintype "passive"))
    )
    (net (code "73") (name "unconnected-(JP1-Pad16)") (class "Default")
      (node (ref "JP1") (pin "16") (pinfunction "16_16") (pintype "passive"))
    )
    (net (code "74") (name "unconnected-(JP1-Pad18)") (class "Default")
      (node (ref "JP1") (pin "18") (pinfunction "18_18") (pintype "passive"))
    )
    (net (code "75") (name "unconnected-(JP1-Pad20)") (class "Default")
      (node (ref "JP1") (pin "20") (pinfunction "20_20") (pintype "passive"))
    )
    (net (code "76") (name "unconnected-(JP1-Pad22)") (class "Default")
      (node (ref "JP1") (pin "22") (pinfunction "22_22") (pintype "passive"))
    )
    (net (code "77") (name "unconnected-(JP1-Pad23)") (class "Default")
      (node (ref "JP1") (pin "23") (pinfunction "23_23") (pintype "passive"))
    )
    (net (code "78") (name "unconnected-(JP1-Pad25)") (class "Default")
      (node (ref "JP1") (pin "25") (pinfunction "25_25") (pintype "passive"))
    )
    (net (code "79") (name "unconnected-(JP1-Pad27)") (class "Default")
      (node (ref "JP1") (pin "27") (pinfunction "27_27") (pintype "passive"))
    )
    (net (code "80") (name "unconnected-(JP1-Pad29)") (class "Default")
      (node (ref "JP1") (pin "29") (pinfunction "29_29") (pintype "passive"))
    )
    (net (code "81") (name "unconnected-(JP2-Pad2)") (class "Default")
      (node (ref "JP2") (pin "2") (pinfunction "2_2") (pintype "passive"))
    )
    (net (code "82") (name "unconnected-(JP2-Pad4)") (class "Default")
      (node (ref "JP2") (pin "4") (pinfunction "4_4") (pintype "passive"))
    )
    (net (code "83") (name "unconnected-(JP2-Pad8)") (class "Default")
      (node (ref "JP2") (pin "8") (pinfunction "8_8") (pintype "passive"))
    )
    (net (code "84") (name "unconnected-(JP2-Pad9)") (class "Default")
      (node (ref "JP2") (pin "9") (pinfunction "9_9") (pintype "passive"))
    )
    (net (code "85") (name "unconnected-(JP2-Pad11)") (class "Default")
      (node (ref "JP2") (pin "11") (pinfunction "11_11") (pintype "passive"))
    )
    (net (code "86") (name "unconnected-(JP2-Pad20)") (class "Default")
      (node (ref "JP2") (pin "20") (pinfunction "20_20") (pintype "passive"))
    )
  )
)
